# wemos_sense.net
KiCad netlist of a schematic drawn in EAGLE
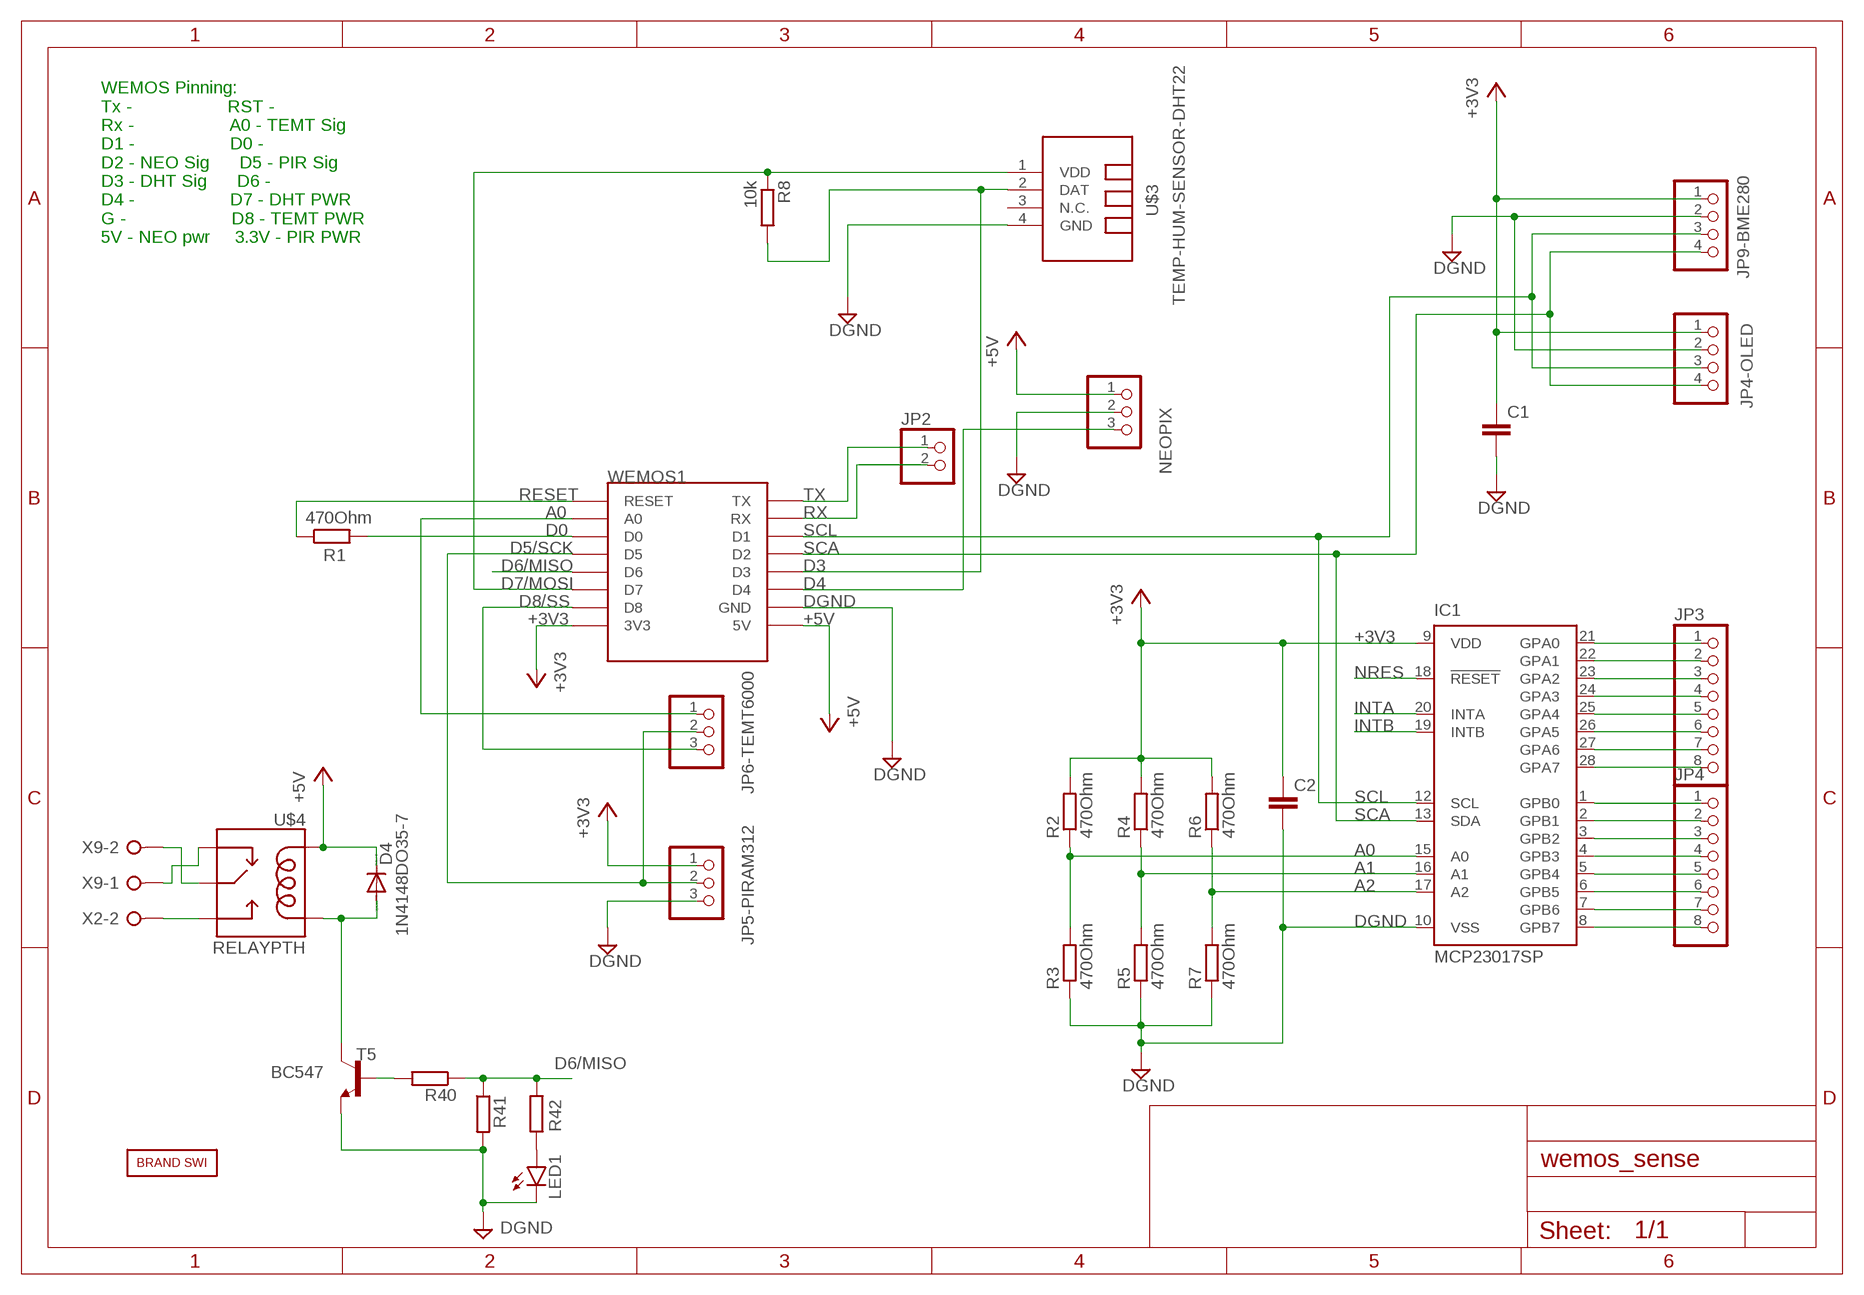
[diagram p0: schematic, sheet 1]

(export (version "E")
  (design (tool "Eeschema 10.0.6"))
  (components
    (comp (ref "C1")
      (value "C-EUC1210")
      (footprint "eagle-import:C1210")
      (libsource (lib "eagle-import") (part "C-EUC1210"))
    )
    (comp (ref "C2")
      (value "C-EUC1210")
      (footprint "eagle-import:C1210")
      (libsource (lib "eagle-import") (part "C-EUC1210"))
    )
    (comp (ref "D4")
      (value "1N4148DO35-7")
      (footprint "eagle-import:DO35-7")
      (libsource (lib "eagle-import") (part "1N4148DO35-7"))
    )
    (comp (ref "IC1")
      (value "MCP23017SP")
      (footprint "eagle-import:DIL28-3")
      (fields (field (name "MF") "MICROCHIP") (field (name "MPN") "MCP23017-E/SP"))
      (libsource (lib "eagle-import") (part "MCP23017SP"))
    )
    (comp (ref "JP2")
      (value "PINHD-1X2")
      (footprint "eagle-import:1X02")
      (libsource (lib "eagle-import") (part "PINHD-1X2"))
    )
    (comp (ref "JP3")
      (value "PINHD-1X8")
      (footprint "eagle-import:1X08")
      (libsource (lib "eagle-import") (part "PINHD-1X8"))
    )
    (comp (ref "JP4")
      (value "PINHD-1X8")
      (footprint "eagle-import:1X08")
      (libsource (lib "eagle-import") (part "PINHD-1X8"))
    )
    (comp (ref "JP4-OLED")
      (value "PINHD-1X4")
      (footprint "eagle-import:1X04")
      (libsource (lib "eagle-import") (part "PINHD-1X4"))
    )
    (comp (ref "JP5-PIRAM312")
      (value "PINHD-1X3")
      (footprint "eagle-import:1X03")
      (libsource (lib "eagle-import") (part "PINHD-1X3"))
    )
    (comp (ref "JP6-TEMT6000")
      (value "PINHD-1X3")
      (footprint "eagle-import:1X03")
      (libsource (lib "eagle-import") (part "PINHD-1X3"))
    )
    (comp (ref "JP9-BME280")
      (value "PINHD-1X4")
      (footprint "eagle-import:1X04")
      (libsource (lib "eagle-import") (part "PINHD-1X4"))
    )
    (comp (ref "LED1")
      (value "LED3MM")
      (footprint "eagle-import:LED3MM")
      (libsource (lib "eagle-import") (part "LED3MM"))
    )
    (comp (ref "NEOPIX")
      (value "PINHD-1X3")
      (footprint "eagle-import:1X03")
      (libsource (lib "eagle-import") (part "PINHD-1X3"))
    )
    (comp (ref "R1")
      (value "470Ohm")
      (footprint "eagle-import:R0805")
      (libsource (lib "eagle-import") (part "R-EU_R0805"))
    )
    (comp (ref "R2")
      (value "470Ohm")
      (footprint "eagle-import:R0805")
      (libsource (lib "eagle-import") (part "R-EU_R0805"))
    )
    (comp (ref "R3")
      (value "470Ohm")
      (footprint "eagle-import:R0805")
      (libsource (lib "eagle-import") (part "R-EU_R0805"))
    )
    (comp (ref "R4")
      (value "470Ohm")
      (footprint "eagle-import:R0805")
      (libsource (lib "eagle-import") (part "R-EU_R0805"))
    )
    (comp (ref "R5")
      (value "470Ohm")
      (footprint "eagle-import:R0805")
      (libsource (lib "eagle-import") (part "R-EU_R0805"))
    )
    (comp (ref "R6")
      (value "470Ohm")
      (footprint "eagle-import:R0805")
      (libsource (lib "eagle-import") (part "R-EU_R0805"))
    )
    (comp (ref "R7")
      (value "470Ohm")
      (footprint "eagle-import:R0805")
      (libsource (lib "eagle-import") (part "R-EU_R0805"))
    )
    (comp (ref "R8")
      (value "10k")
      (footprint "eagle-import:R0805")
      (libsource (lib "eagle-import") (part "R-EU_R0805"))
    )
    (comp (ref "R40")
      (value "R-EU_R0805")
      (footprint "eagle-import:R0805")
      (libsource (lib "eagle-import") (part "R-EU_R0805"))
    )
    (comp (ref "R41")
      (value "R-EU_R0805")
      (footprint "eagle-import:R0805")
      (libsource (lib "eagle-import") (part "R-EU_R0805"))
    )
    (comp (ref "R42")
      (value "R-EU_R0805")
      (footprint "eagle-import:R0805")
      (libsource (lib "eagle-import") (part "R-EU_R0805"))
    )
    (comp (ref "T5")
      (value "BC547")
      (footprint "eagle-import:TO92")
      (libsource (lib "eagle-import") (part "BC547"))
    )
    (comp (ref "U$2")
      (value "BRAND_SWI5X7")
      (footprint "eagle-import:BRAND_SWI_5X7")
      (libsource (lib "eagle-import") (part "BRAND_SWI5X7"))
    )
    (comp (ref "U$3")
      (value "TEMP-HUM-SENSOR-DHT22")
      (footprint "eagle-import:TEMP-HUM-SENSOR-DHT22")
      (libsource (lib "eagle-import") (part "TEMP-HUM-SENSOR-DHT22"))
    )
    (comp (ref "U$4")
      (value "RELAYPTH")
      (footprint "eagle-import:SRD-05VDC-SL-C")
      (libsource (lib "eagle-import") (part "RELAYPTH"))
    )
    (comp (ref "WEMOS1")
      (value "WEMOS-D1-MINI")
      (footprint "eagle-import:WEMOS-D1-MINI")
      (libsource (lib "eagle-import") (part "WEMOS-D1-MINI"))
    )
    (comp (ref "X2")
      (value "W237-02P")
      (footprint "eagle-import:W237-132")
      (libsource (lib "eagle-import") (part "W237-02P"))
    )
    (comp (ref "X9")
      (value "W237-02P")
      (footprint "eagle-import:W237-132")
      (libsource (lib "eagle-import") (part "W237-02P"))
    )
  )
  (nets
    (net (code "1") (name "+3V3") (class "Default")
      (node (ref "C1") (pin "1") (pinfunction "1_1") (pintype "passive"))
      (node (ref "C2") (pin "1") (pinfunction "1_1") (pintype "passive"))
      (node (ref "IC1") (pin "9") (pinfunction "VDD_9") (pintype "power_in"))
      (node (ref "JP4-OLED") (pin "1") (pinfunction "1_1") (pintype "passive"))
      (node (ref "JP5-PIRAM312") (pin "1") (pinfunction "1_1") (pintype "passive"))
      (node (ref "JP9-BME280") (pin "1") (pinfunction "1_1") (pintype "passive"))
      (node (ref "R2") (pin "2") (pinfunction "2_2") (pintype "passive"))
      (node (ref "R4") (pin "2") (pinfunction "2_2") (pintype "passive"))
      (node (ref "R6") (pin "2") (pinfunction "2_2") (pintype "passive"))
      (node (ref "WEMOS1") (pin "3V3") (pinfunction "3V3_3V3") (pintype "bidirectional"))
    )
    (net (code "2") (name "+5V") (class "Default")
      (node (ref "D4") (pin "C") (pinfunction "C_C") (pintype "passive"))
      (node (ref "NEOPIX") (pin "1") (pinfunction "1_1") (pintype "passive"))
      (node (ref "U$4") (pin "COIL1") (pinfunction "COIL1_COIL1") (pintype "bidirectional"))
      (node (ref "WEMOS1") (pin "5V") (pinfunction "5V_5V") (pintype "bidirectional"))
    )
    (net (code "3") (name "/A0") (class "Default")
      (node (ref "IC1") (pin "15") (pinfunction "A0_15") (pintype "input"))
      (node (ref "JP6-TEMT6000") (pin "1") (pinfunction "1_1") (pintype "passive"))
      (node (ref "R2") (pin "1") (pinfunction "1_1") (pintype "passive"))
      (node (ref "R3") (pin "2") (pinfunction "2_2") (pintype "passive"))
      (node (ref "WEMOS1") (pin "A0") (pinfunction "A0_A0") (pintype "bidirectional"))
    )
    (net (code "4") (name "/A1") (class "Default")
      (node (ref "IC1") (pin "16") (pinfunction "A1_16") (pintype "input"))
      (node (ref "R4") (pin "1") (pinfunction "1_1") (pintype "passive"))
      (node (ref "R5") (pin "2") (pinfunction "2_2") (pintype "passive"))
    )
    (net (code "5") (name "/A2") (class "Default")
      (node (ref "IC1") (pin "17") (pinfunction "A2_17") (pintype "input"))
      (node (ref "R6") (pin "1") (pinfunction "1_1") (pintype "passive"))
      (node (ref "R7") (pin "2") (pinfunction "2_2") (pintype "passive"))
    )
    (net (code "6") (name "/D0") (class "Default")
      (node (ref "R1") (pin "2") (pinfunction "2_2") (pintype "passive"))
      (node (ref "WEMOS1") (pin "D0") (pinfunction "D0_D0") (pintype "bidirectional"))
    )
    (net (code "7") (name "/D3") (class "Default")
      (node (ref "R8") (pin "2") (pinfunction "2_2") (pintype "passive"))
      (node (ref "U$3") (pin "2") (pinfunction "DAT_2") (pintype "bidirectional"))
      (node (ref "WEMOS1") (pin "D3") (pinfunction "D3_D3") (pintype "bidirectional"))
    )
    (net (code "8") (name "/D4") (class "Default")
      (node (ref "NEOPIX") (pin "3") (pinfunction "3_3") (pintype "passive"))
      (node (ref "WEMOS1") (pin "D4") (pinfunction "D4_D4") (pintype "bidirectional"))
    )
    (net (code "9") (name "/D5{slash}SCK") (class "Default")
      (node (ref "JP5-PIRAM312") (pin "2") (pinfunction "2_2") (pintype "passive"))
      (node (ref "JP6-TEMT6000") (pin "2") (pinfunction "2_2") (pintype "passive"))
      (node (ref "WEMOS1") (pin "D5") (pinfunction "D5_D5") (pintype "bidirectional"))
    )
    (net (code "10") (name "/D6{slash}MISO") (class "Default")
      (node (ref "R40") (pin "1") (pinfunction "1_1") (pintype "passive"))
      (node (ref "R41") (pin "1") (pinfunction "1_1") (pintype "passive"))
      (node (ref "R42") (pin "2") (pinfunction "2_2") (pintype "passive"))
      (node (ref "WEMOS1") (pin "D6") (pinfunction "D6_D6") (pintype "bidirectional"))
    )
    (net (code "11") (name "/D7{slash}MOSI") (class "Default")
      (node (ref "R8") (pin "1") (pinfunction "1_1") (pintype "passive"))
      (node (ref "U$3") (pin "1") (pinfunction "VDD_1") (pintype "power_in"))
      (node (ref "WEMOS1") (pin "D7") (pinfunction "D7_D7") (pintype "bidirectional"))
    )
    (net (code "12") (name "/D8{slash}SS") (class "Default")
      (node (ref "JP6-TEMT6000") (pin "3") (pinfunction "3_3") (pintype "passive"))
      (node (ref "WEMOS1") (pin "D8") (pinfunction "D8_D8") (pintype "bidirectional"))
    )
    (net (code "13") (name "/INTA") (class "Default")
      (node (ref "IC1") (pin "20") (pinfunction "INTA_20") (pintype "output"))
    )
    (net (code "14") (name "/INTB") (class "Default")
      (node (ref "IC1") (pin "19") (pinfunction "INTB_19") (pintype "output"))
    )
    (net (code "15") (name "/NRES") (class "Default")
      (node (ref "IC1") (pin "18") (pinfunction "~{RESET}_18") (pintype "input"))
    )
    (net (code "16") (name "/RESET") (class "Default")
      (node (ref "R1") (pin "1") (pinfunction "1_1") (pintype "passive"))
      (node (ref "WEMOS1") (pin "RESET") (pinfunction "RESET_RESET") (pintype "bidirectional"))
    )
    (net (code "17") (name "/RX") (class "Default")
      (node (ref "JP2") (pin "2") (pinfunction "2_2") (pintype "passive"))
      (node (ref "WEMOS1") (pin "RX") (pinfunction "RX_RX") (pintype "bidirectional"))
    )
    (net (code "18") (name "/SCA") (class "Default")
      (node (ref "IC1") (pin "13") (pinfunction "SDA_13") (pintype "bidirectional"))
      (node (ref "JP4-OLED") (pin "4") (pinfunction "4_4") (pintype "passive"))
      (node (ref "JP9-BME280") (pin "4") (pinfunction "4_4") (pintype "passive"))
      (node (ref "WEMOS1") (pin "D2") (pinfunction "D2_D2") (pintype "bidirectional"))
    )
    (net (code "19") (name "/SCL") (class "Default")
      (node (ref "IC1") (pin "12") (pinfunction "SCL_12") (pintype "input"))
      (node (ref "JP4-OLED") (pin "3") (pinfunction "3_3") (pintype "passive"))
      (node (ref "JP9-BME280") (pin "3") (pinfunction "3_3") (pintype "passive"))
      (node (ref "WEMOS1") (pin "D1") (pinfunction "D1_D1") (pintype "bidirectional"))
    )
    (net (code "20") (name "/TX") (class "Default")
      (node (ref "JP2") (pin "1") (pinfunction "1_1") (pintype "passive"))
      (node (ref "WEMOS1") (pin "TX") (pinfunction "TX_TX") (pintype "bidirectional"))
    )
    (net (code "21") (name "DGND") (class "Default")
      (node (ref "C1") (pin "2") (pinfunction "2_2") (pintype "passive"))
      (node (ref "C2") (pin "2") (pinfunction "2_2") (pintype "passive"))
      (node (ref "IC1") (pin "10") (pinfunction "VSS_10") (pintype "power_in"))
      (node (ref "JP4-OLED") (pin "2") (pinfunction "2_2") (pintype "passive"))
      (node (ref "JP5-PIRAM312") (pin "3") (pinfunction "3_3") (pintype "passive"))
      (node (ref "JP9-BME280") (pin "2") (pinfunction "2_2") (pintype "passive"))
      (node (ref "LED1") (pin "K") (pinfunction "C_K") (pintype "passive"))
      (node (ref "NEOPIX") (pin "2") (pinfunction "2_2") (pintype "passive"))
      (node (ref "R3") (pin "1") (pinfunction "1_1") (pintype "passive"))
      (node (ref "R41") (pin "2") (pinfunction "2_2") (pintype "passive"))
      (node (ref "R5") (pin "1") (pinfunction "1_1") (pintype "passive"))
      (node (ref "R7") (pin "1") (pinfunction "1_1") (pintype "passive"))
      (node (ref "T5") (pin "1") (pinfunction "E_1") (pintype "passive"))
      (node (ref "U$3") (pin "4") (pinfunction "GND_4") (pintype "power_in"))
      (node (ref "WEMOS1") (pin "GND") (pinfunction "GND_GND") (pintype "bidirectional"))
    )
    (net (code "22") (name "Net-(IC1-GPA0)") (class "Default")
      (node (ref "IC1") (pin "21") (pinfunction "GPA0_21") (pintype "bidirectional"))
      (node (ref "JP3") (pin "1") (pinfunction "1_1") (pintype "passive"))
    )
    (net (code "23") (name "Net-(IC1-GPA1)") (class "Default")
      (node (ref "IC1") (pin "22") (pinfunction "GPA1_22") (pintype "bidirectional"))
      (node (ref "JP3") (pin "2") (pinfunction "2_2") (pintype "passive"))
    )
    (net (code "24") (name "Net-(IC1-GPA2)") (class "Default")
      (node (ref "IC1") (pin "23") (pinfunction "GPA2_23") (pintype "bidirectional"))
      (node (ref "JP3") (pin "3") (pinfunction "3_3") (pintype "passive"))
    )
    (net (code "25") (name "Net-(IC1-GPA3)") (class "Default")
      (node (ref "IC1") (pin "24") (pinfunction "GPA3_24") (pintype "bidirectional"))
      (node (ref "JP3") (pin "4") (pinfunction "4_4") (pintype "passive"))
    )
    (net (code "26") (name "Net-(IC1-GPA4)") (class "Default")
      (node (ref "IC1") (pin "25") (pinfunction "GPA4_25") (pintype "bidirectional"))
      (node (ref "JP3") (pin "5") (pinfunction "5_5") (pintype "passive"))
    )
    (net (code "27") (name "Net-(IC1-GPA5)") (class "Default")
      (node (ref "IC1") (pin "26") (pinfunction "GPA5_26") (pintype "bidirectional"))
      (node (ref "JP3") (pin "6") (pinfunction "6_6") (pintype "passive"))
    )
    (net (code "28") (name "Net-(IC1-GPA6)") (class "Default")
      (node (ref "IC1") (pin "27") (pinfunction "GPA6_27") (pintype "bidirectional"))
      (node (ref "JP3") (pin "7") (pinfunction "7_7") (pintype "passive"))
    )
    (net (code "29") (name "Net-(IC1-GPA7)") (class "Default")
      (node (ref "IC1") (pin "28") (pinfunction "GPA7_28") (pintype "bidirectional"))
      (node (ref "JP3") (pin "8") (pinfunction "8_8") (pintype "passive"))
    )
    (net (code "30") (name "Net-(IC1-GPB0)") (class "Default")
      (node (ref "IC1") (pin "1") (pinfunction "GPB0_1") (pintype "bidirectional"))
      (node (ref "JP4") (pin "1") (pinfunction "1_1") (pintype "passive"))
    )
    (net (code "31") (name "Net-(IC1-GPB1)") (class "Default")
      (node (ref "IC1") (pin "2") (pinfunction "GPB1_2") (pintype "bidirectional"))
      (node (ref "JP4") (pin "2") (pinfunction "2_2") (pintype "passive"))
    )
    (net (code "32") (name "Net-(IC1-GPB2)") (class "Default")
      (node (ref "IC1") (pin "3") (pinfunction "GPB2_3") (pintype "bidirectional"))
      (node (ref "JP4") (pin "3") (pinfunction "3_3") (pintype "passive"))
    )
    (net (code "33") (name "Net-(IC1-GPB3)") (class "Default")
      (node (ref "IC1") (pin "4") (pinfunction "GPB3_4") (pintype "bidirectional"))
      (node (ref "JP4") (pin "4") (pinfunction "4_4") (pintype "passive"))
    )
    (net (code "34") (name "Net-(IC1-GPB4)") (class "Default")
      (node (ref "IC1") (pin "5") (pinfunction "GPB4_5") (pintype "bidirectional"))
      (node (ref "JP4") (pin "5") (pinfunction "5_5") (pintype "passive"))
    )
    (net (code "35") (name "Net-(IC1-GPB5)") (class "Default")
      (node (ref "IC1") (pin "6") (pinfunction "GPB5_6") (pintype "bidirectional"))
      (node (ref "JP4") (pin "6") (pinfunction "6_6") (pintype "passive"))
    )
    (net (code "36") (name "Net-(IC1-GPB6)") (class "Default")
      (node (ref "IC1") (pin "7") (pinfunction "GPB6_7") (pintype "bidirectional"))
      (node (ref "JP4") (pin "7") (pinfunction "7_7") (pintype "passive"))
    )
    (net (code "37") (name "Net-(IC1-GPB7)") (class "Default")
      (node (ref "IC1") (pin "8") (pinfunction "GPB7_8") (pintype "bidirectional"))
      (node (ref "JP4") (pin "8") (pinfunction "8_8") (pintype "passive"))
    )
    (net (code "38") (name "Net-(LED1-PadA)") (class "Default")
      (node (ref "LED1") (pin "A") (pinfunction "A_A") (pintype "passive"))
      (node (ref "R42") (pin "1") (pinfunction "1_1") (pintype "passive"))
    )
    (net (code "39") (name "Net-(T5-B)") (class "Default")
      (node (ref "R40") (pin "2") (pinfunction "2_2") (pintype "passive"))
      (node (ref "T5") (pin "2") (pinfunction "B_2") (pintype "passive"))
    )
    (net (code "40") (name "Net-(T5-C)") (class "Default")
      (node (ref "D4") (pin "A") (pinfunction "A_A") (pintype "passive"))
      (node (ref "T5") (pin "3") (pinfunction "C_3") (pintype "passive"))
      (node (ref "U$4") (pin "COIL0") (pinfunction "COIL0_COIL0") (pintype "bidirectional"))
    )
    (net (code "41") (name "Net-(U$4-SWCLOSE)") (class "Default")
      (node (ref "U$4") (pin "SWCLOSED") (pinfunction "SWCLOSE_SWCLOSED") (pintype "bidirectional"))
      (node (ref "X9") (pin "1") (pinfunction "KL_1") (pintype "passive"))
    )
    (net (code "42") (name "Net-(X2B-KL)") (class "Default")
      (node (ref "U$4") (pin "SWOPEN") (pinfunction "SWOPEN_SWOPEN") (pintype "bidirectional"))
      (node (ref "X2") (pin "2") (pinfunction "KL_2") (pintype "passive"))
    )
    (net (code "43") (name "Net-(X9B-KL)") (class "Default")
      (node (ref "U$4") (pin "SWCOMMON") (pinfunction "SWCOMMON_SWCOMMON") (pintype "bidirectional"))
      (node (ref "X9") (pin "2") (pinfunction "KL_2") (pintype "passive"))
    )
    (net (code "44") (name "unconnected-(U$3-N.C.-Pad3)") (class "Default")
      (node (ref "U$3") (pin "3") (pinfunction "N.C._3") (pintype "passive"))
    )
  )
)
